# SIM_SCHE.net
KiCad netlist of a schematic drawn in Altium Designer
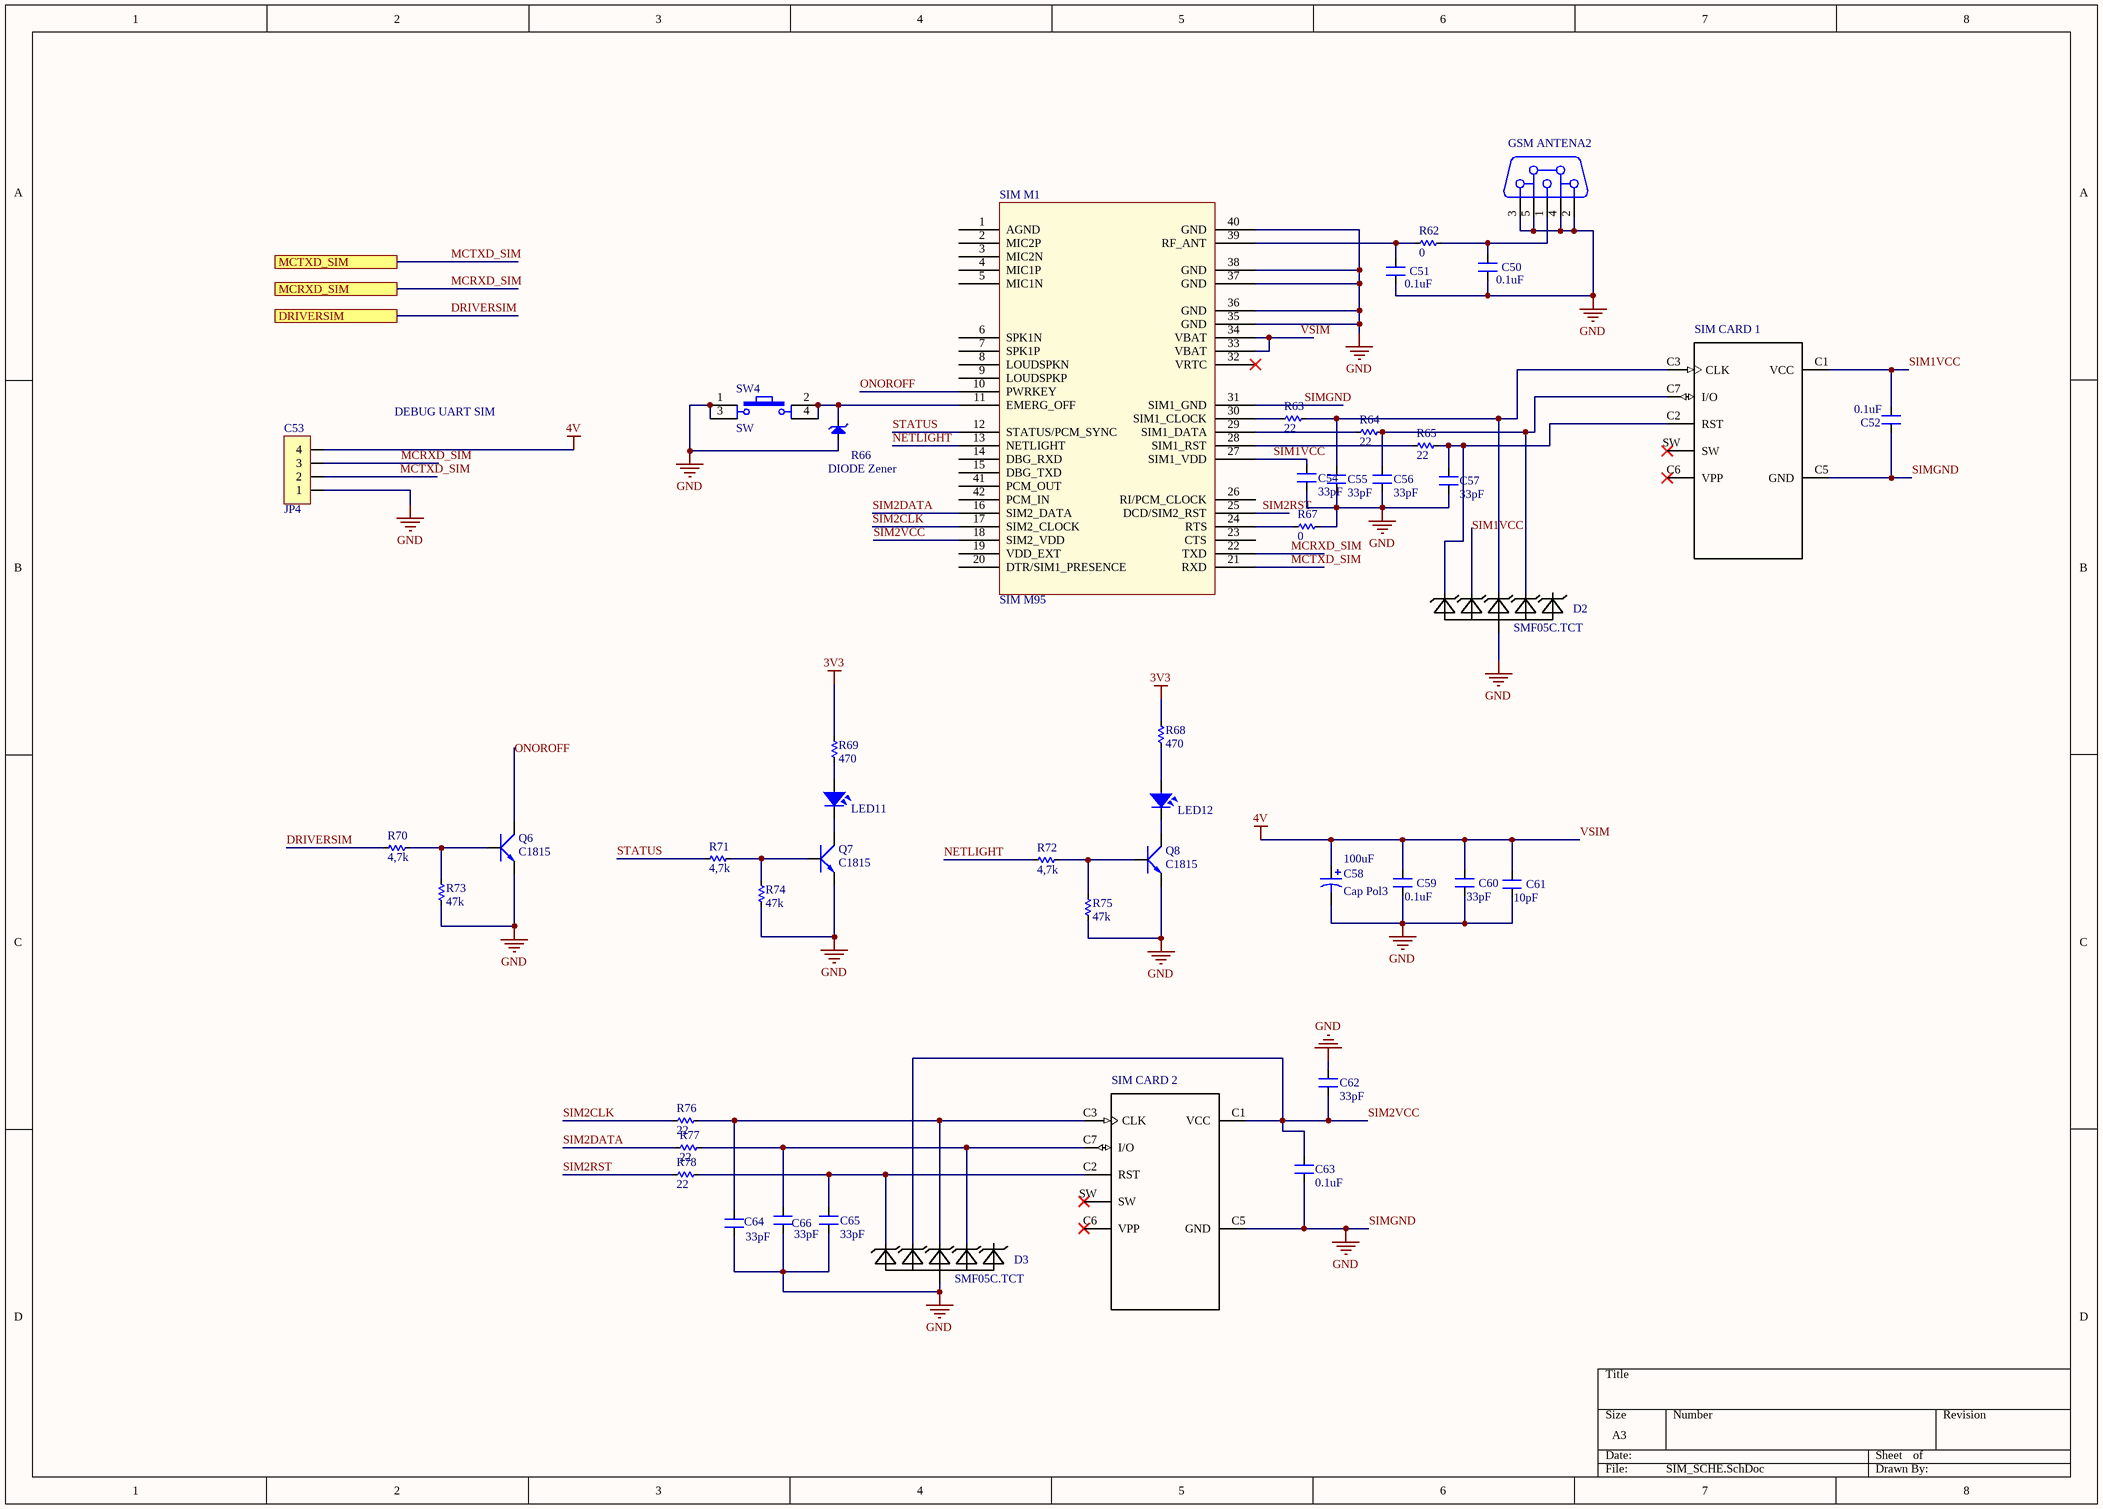
[diagram p0: SIM_SCHE.SchDoc]

(export (version "E")
  (design (tool "Eeschema 10.0.6"))
  (components
    (comp (ref "C50")
      (value "0.1uF")
      (footprint "res 0805 - duplicate")
      (description "Cap SMD")
      (libsource (lib "PART") (part "CM"))
    )
    (comp (ref "C51")
      (value "0.1uF")
      (footprint "res 0805 - duplicate")
      (description "Cap SMD")
      (libsource (lib "PART") (part "CM"))
    )
    (comp (ref "C52")
      (value "0.1uF")
      (footprint "res 0805 - duplicate")
      (description "Cap SMD")
      (libsource (lib "PART") (part "CM"))
    )
    (comp (ref "C53")
      (value "JP4")
      (footprint "JP4-C1T")
      (description "WR-PHD 2.54 mm Angled Socket Header")
      (fields
        (field (name "MANUFACTURER") "Würth Elektronik eiSos GmbH")
        (field (name "PARTNO") "613004143121")
        (field (name "CREATED BY") "Karrer Zheng")
      )
      (libsource (lib "LIBRARYabc") (part "JP4"))
    )
    (comp (ref "C54")
      (value "33pF")
      (footprint "res 0805 - duplicate")
      (fields (field (name "DESIGNED BY") "VanDungEvn"))
      (libsource (lib "syhaunguyen") (part "CN"))
    )
    (comp (ref "C55")
      (value "33pF")
      (footprint "res 0805 - duplicate")
      (fields (field (name "DESIGNED BY") "VanDungEvn"))
      (libsource (lib "syhaunguyen") (part "CN"))
    )
    (comp (ref "C56")
      (value "33pF")
      (footprint "res 0805 - duplicate")
      (fields (field (name "DESIGNED BY") "VanDungEvn"))
      (libsource (lib "syhaunguyen") (part "CN"))
    )
    (comp (ref "C57")
      (value "33pF")
      (footprint "res 0805 - duplicate")
      (fields (field (name "DESIGNED BY") "VanDungEvn"))
      (libsource (lib "syhaunguyen") (part "CN"))
    )
    (comp (ref "C58")
      (value "Cap Pol3")
      (footprint "cap_100uf")
      (description "Polarized Capacitor (Surface Mount)")
      (fields (field (name "ALTIUM_VALUE") "100uF") (field (name "PUBLISHER") "Altium Limited"))
      (libsource (lib "Miscellaneous Devices") (part "Cap Pol3"))
    )
    (comp (ref "C59")
      (value "0.1uF")
      (footprint "res 0805 - duplicate")
      (description "Cap SMD")
      (libsource (lib "PART") (part "CM"))
    )
    (comp (ref "C60")
      (value "33pF")
      (footprint "res 0805 - duplicate")
      (description "Cap SMD")
      (libsource (lib "PART") (part "CM"))
    )
    (comp (ref "C61")
      (value "10pF")
      (footprint "res 0805 - duplicate")
      (description "Cap SMD")
      (libsource (lib "PART") (part "CM"))
    )
    (comp (ref "C62")
      (value "33pF")
      (footprint "res 0805 - duplicate")
      (fields (field (name "DESIGNED BY") "VanDungEvn"))
      (libsource (lib "syhaunguyen") (part "CN"))
    )
    (comp (ref "C63")
      (value "0.1uF")
      (footprint "res 0805 - duplicate")
      (fields (field (name "DESIGNED BY") "VanDungEvn"))
      (libsource (lib "syhaunguyen") (part "CN"))
    )
    (comp (ref "C64")
      (value "33pF")
      (footprint "res 0805 - duplicate")
      (fields (field (name "DESIGNED BY") "VanDungEvn"))
      (libsource (lib "syhaunguyen") (part "CN"))
    )
    (comp (ref "C65")
      (value "33pF")
      (footprint "res 0805 - duplicate")
      (fields (field (name "DESIGNED BY") "VanDungEvn"))
      (libsource (lib "syhaunguyen") (part "CN"))
    )
    (comp (ref "C66")
      (value "33pF")
      (footprint "res 0805 - duplicate")
      (fields (field (name "DESIGNED BY") "VanDungEvn"))
      (libsource (lib "syhaunguyen") (part "CN"))
    )
    (comp (ref "D2")
      (value "SMF05C.TCT")
      (footprint "SC70-6")
      (fields (field (name "MF") "Semtech"))
      (libsource (lib "SMF05C.TCT") (part "SMF05C.TCT"))
    )
    (comp (ref "D3")
      (value "SMF05C.TCT")
      (footprint "SC70-6")
      (fields (field (name "MF") "Semtech"))
      (libsource (lib "SMF05C.TCT") (part "SMF05C.TCT"))
    )
    (comp (ref "GSM ANTENA2")
      (value "~")
      (footprint "anten")
      (description "CONNECTOR ANTEN")
      (fields
        (field (name "PARTNO") "210111003")
        (field (name "MANUFACTURER") "Würth Elektronik eiSos GmbH")
        (field (name "CREATED BY") "Christin Zierenner")
      )
      (libsource (lib "LIBRARYabc") (part "CON Ant"))
    )
    (comp (ref "LED11")
      (value "LED")
      (footprint "res 0805 - duplicate")
      (libsource (lib "LIBRARYabc") (part "LED SMD"))
    )
    (comp (ref "LED12")
      (value "LED")
      (footprint "res 0805 - duplicate")
      (libsource (lib "LIBRARYabc") (part "LED SMD"))
    )
    (comp (ref "Q6")
      (value "C1815")
      (footprint "SOT23B")
      (description "NPN 600mW, ECB")
      (libsource (lib "syhaunguyen") (part "C1815"))
    )
    (comp (ref "Q7")
      (value "C1815")
      (footprint "SOT23B")
      (description "NPN 600mW, ECB")
      (libsource (lib "syhaunguyen") (part "C1815"))
    )
    (comp (ref "Q8")
      (value "C1815")
      (footprint "SOT23B")
      (description "NPN 600mW, ECB")
      (libsource (lib "syhaunguyen") (part "C1815"))
    )
    (comp (ref "R62")
      (value "0")
      (footprint "res 0805 - duplicate")
      (description "Resistor")
      (fields
        (field (name "MANUFACTURER") "Generic Components")
        (field (name "PUBLISHER") "Altium Hobart Technology Centre")
      )
      (libsource (lib "LIBRARYabc") (part "Res-SMD"))
    )
    (comp (ref "R63")
      (value "22")
      (footprint "res 0805 - duplicate")
      (description "Resistor")
      (fields
        (field (name "MANUFACTURER") "Generic Components")
        (field (name "PUBLISHER") "Altium Hobart Technology Centre")
      )
      (libsource (lib "LIBRARYabc") (part "Res-SMD"))
    )
    (comp (ref "R64")
      (value "22")
      (footprint "res 0805 - duplicate")
      (description "Resistor")
      (fields
        (field (name "MANUFACTURER") "Generic Components")
        (field (name "PUBLISHER") "Altium Hobart Technology Centre")
      )
      (libsource (lib "LIBRARYabc") (part "Res-SMD"))
    )
    (comp (ref "R65")
      (value "22")
      (footprint "res 0805 - duplicate")
      (description "Resistor")
      (fields
        (field (name "MANUFACTURER") "Generic Components")
        (field (name "PUBLISHER") "Altium Hobart Technology Centre")
      )
      (libsource (lib "LIBRARYabc") (part "Res-SMD"))
    )
    (comp (ref "R66")
      (value "DIODE Zener")
      (footprint "diot zenner SOD123")
      (description "Zenner")
      (libsource (lib "LIBRARYabc") (part "DIODE Zener"))
    )
    (comp (ref "R67")
      (value "0")
      (footprint "res 0805 - duplicate")
      (description "Resistor")
      (fields
        (field (name "MANUFACTURER") "Generic Components")
        (field (name "PUBLISHER") "Altium Hobart Technology Centre")
      )
      (libsource (lib "LIBRARYabc") (part "Res-SMD"))
    )
    (comp (ref "R68")
      (value "470")
      (footprint "res 0805 - duplicate")
      (description "Resistor")
      (fields
        (field (name "MANUFACTURER") "Generic Components")
        (field (name "PUBLISHER") "Altium Hobart Technology Centre")
      )
      (libsource (lib "LIBRARYabc") (part "Res-SMD"))
    )
    (comp (ref "R69")
      (value "470")
      (footprint "res 0805 - duplicate")
      (description "Resistor")
      (fields
        (field (name "MANUFACTURER") "Generic Components")
        (field (name "PUBLISHER") "Altium Hobart Technology Centre")
      )
      (libsource (lib "LIBRARYabc") (part "Res-SMD"))
    )
    (comp (ref "R70")
      (value "4,7k")
      (footprint "res 0805 - duplicate")
      (description "Resistor")
      (fields
        (field (name "MANUFACTURER") "Generic Components")
        (field (name "PUBLISHER") "Altium Hobart Technology Centre")
      )
      (libsource (lib "LIBRARYabc") (part "Res-SMD"))
    )
    (comp (ref "R71")
      (value "4,7k")
      (footprint "res 0805 - duplicate")
      (description "Resistor")
      (fields
        (field (name "MANUFACTURER") "Generic Components")
        (field (name "PUBLISHER") "Altium Hobart Technology Centre")
      )
      (libsource (lib "LIBRARYabc") (part "Res-SMD"))
    )
    (comp (ref "R72")
      (value "4,7k")
      (footprint "res 0805 - duplicate")
      (description "Resistor")
      (fields
        (field (name "MANUFACTURER") "Generic Components")
        (field (name "PUBLISHER") "Altium Hobart Technology Centre")
      )
      (libsource (lib "LIBRARYabc") (part "Res-SMD"))
    )
    (comp (ref "R73")
      (value "47k")
      (footprint "res 0805 - duplicate")
      (description "Resistor")
      (fields
        (field (name "MANUFACTURER") "Generic Components")
        (field (name "PUBLISHER") "Altium Hobart Technology Centre")
      )
      (libsource (lib "LIBRARYabc") (part "Res-SMD"))
    )
    (comp (ref "R74")
      (value "47k")
      (footprint "res 0805 - duplicate")
      (description "Resistor")
      (fields
        (field (name "MANUFACTURER") "Generic Components")
        (field (name "PUBLISHER") "Altium Hobart Technology Centre")
      )
      (libsource (lib "LIBRARYabc") (part "Res-SMD"))
    )
    (comp (ref "R75")
      (value "47k")
      (footprint "res 0805 - duplicate")
      (description "Resistor")
      (fields
        (field (name "MANUFACTURER") "Generic Components")
        (field (name "PUBLISHER") "Altium Hobart Technology Centre")
      )
      (libsource (lib "LIBRARYabc") (part "Res-SMD"))
    )
    (comp (ref "R76")
      (value "22")
      (footprint "res 0805 - duplicate")
      (description "Resistor")
      (fields
        (field (name "MANUFACTURER") "Generic Components")
        (field (name "PUBLISHER") "Altium Hobart Technology Centre")
      )
      (libsource (lib "LIBRARYabc") (part "Res-SMD"))
    )
    (comp (ref "R77")
      (value "22")
      (footprint "res 0805 - duplicate")
      (description "Resistor")
      (fields
        (field (name "MANUFACTURER") "Generic Components")
        (field (name "PUBLISHER") "Altium Hobart Technology Centre")
      )
      (libsource (lib "LIBRARYabc") (part "Res-SMD"))
    )
    (comp (ref "R78")
      (value "22")
      (footprint "res 0805 - duplicate")
      (description "Resistor")
      (fields
        (field (name "MANUFACTURER") "Generic Components")
        (field (name "PUBLISHER") "Altium Hobart Technology Centre")
      )
      (libsource (lib "LIBRARYabc") (part "Res-SMD"))
    )
    (comp (ref "SIM CARD 1")
      (value "2199337-5")
      (footprint "SIMCARD")
      (description "ASS'Y FOR MICRO SIM H1.18 8POS _EMBOSS_")
      (fields (field (name "MF") "TE Connectivity"))
      (libsource (lib "2199337-5") (part "2199337-5"))
    )
    (comp (ref "SIM CARD 2")
      (value "2199337-5")
      (footprint "SIMCARD")
      (description "ASS'Y FOR MICRO SIM H1.18 8POS _EMBOSS_")
      (fields (field (name "MF") "TE Connectivity"))
      (libsource (lib "2199337-5") (part "2199337-5"))
    )
    (comp (ref "SIM M1") (value "SIM M95") (footprint "SIM M95") (libsource (lib "Sim M95") (part "SIM M95")))
    (comp (ref "SW4")
      (value "SW")
      (footprint "button")
      (description "Switch button 4 pin")
      (libsource (lib "syhaunguyen") (part "SW4"))
    )
  )
  (nets
    (net (code "1") (name "/DRIVERSIM") (class "Default")
      (node (ref "R70") (pin "2") (pinfunction "2_2") (pintype "passive"))
    )
    (net (code "2") (name "/MCRXD_SIM") (class "Default")
      (node (ref "C53") (pin "3") (pinfunction "3_3") (pintype "passive"))
      (node (ref "SIM M1") (pin "22") (pinfunction "TXD_22") (pintype "passive"))
    )
    (net (code "3") (name "/MCTXD_SIM") (class "Default")
      (node (ref "C53") (pin "2") (pinfunction "2_2") (pintype "passive"))
      (node (ref "SIM M1") (pin "21") (pinfunction "RXD_21") (pintype "passive"))
    )
    (net (code "4") (name "/NETLIGHT") (class "Default")
      (node (ref "R72") (pin "2") (pinfunction "2_2") (pintype "passive"))
      (node (ref "SIM M1") (pin "13") (pinfunction "NETLIGHT_13") (pintype "passive"))
    )
    (net (code "5") (name "/ONOROFF") (class "Default")
      (node (ref "Q6") (pin "2") (pinfunction "C_2") (pintype "passive"))
      (node (ref "SIM M1") (pin "10") (pinfunction "PWRKEY_10") (pintype "passive"))
    )
    (net (code "6") (name "/SIM1VCC") (class "Default")
      (node (ref "C52") (pin "2") (pinfunction "2_2") (pintype "passive"))
      (node (ref "C54") (pin "2") (pinfunction "2_2") (pintype "passive"))
      (node (ref "D2") (pin "3") (pinfunction "C2_3") (pintype "passive"))
      (node (ref "SIM CARD 1") (pin "C1") (pinfunction "VCC_C1") (pintype "power_in"))
      (node (ref "SIM M1") (pin "27") (pinfunction "SIM1_VDD_27") (pintype "passive"))
    )
    (net (code "7") (name "/SIM2CLK") (class "Default")
      (node (ref "R76") (pin "2") (pinfunction "2_2") (pintype "passive"))
      (node (ref "SIM M1") (pin "17") (pinfunction "SIM2_CLOCK_17") (pintype "passive"))
    )
    (net (code "8") (name "/SIM2DATA") (class "Default")
      (node (ref "R77") (pin "2") (pinfunction "2_2") (pintype "passive"))
      (node (ref "SIM M1") (pin "16") (pinfunction "SIM2_DATA_16") (pintype "passive"))
    )
    (net (code "9") (name "/SIM2RST") (class "Default")
      (node (ref "R78") (pin "2") (pinfunction "2_2") (pintype "passive"))
      (node (ref "SIM M1") (pin "25") (pinfunction "DCD/SIM2_RST_25") (pintype "passive"))
    )
    (net (code "10") (name "/SIM2VCC") (class "Default")
      (node (ref "C62") (pin "1") (pinfunction "1_1") (pintype "passive"))
      (node (ref "C63") (pin "2") (pinfunction "2_2") (pintype "passive"))
      (node (ref "D3") (pin "3") (pinfunction "C2_3") (pintype "passive"))
      (node (ref "SIM CARD 2") (pin "C1") (pinfunction "VCC_C1") (pintype "power_in"))
      (node (ref "SIM M1") (pin "18") (pinfunction "SIM2_VDD_18") (pintype "passive"))
    )
    (net (code "11") (name "/STATUS") (class "Default")
      (node (ref "R71") (pin "2") (pinfunction "2_2") (pintype "passive"))
      (node (ref "SIM M1") (pin "12") (pinfunction "STATUS/PCM_SYNC_12") (pintype "passive"))
    )
    (net (code "12") (name "3V3") (class "Default")
      (node (ref "R68") (pin "1") (pinfunction "1_1") (pintype "passive"))
      (node (ref "R69") (pin "1") (pinfunction "1_1") (pintype "passive"))
    )
    (net (code "13") (name "4V") (class "Default")
      (node (ref "C53") (pin "4") (pinfunction "4_4") (pintype "passive"))
      (node (ref "C58") (pin "1") (pinfunction "1_1") (pintype "passive"))
      (node (ref "C59") (pin "2") (pinfunction "2_2") (pintype "passive"))
      (node (ref "C60") (pin "2") (pinfunction "2_2") (pintype "passive"))
      (node (ref "C61") (pin "2") (pinfunction "2_2") (pintype "passive"))
      (node (ref "SIM M1") (pin "33") (pinfunction "VBAT_33") (pintype "passive"))
      (node (ref "SIM M1") (pin "34") (pinfunction "VBAT_34") (pintype "passive"))
    )
    (net (code "14") (name "GND") (class "Default")
      (node (ref "C50") (pin "1") (pinfunction "1_1") (pintype "passive"))
      (node (ref "C51") (pin "1") (pinfunction "1_1") (pintype "passive"))
      (node (ref "C52") (pin "1") (pinfunction "1_1") (pintype "passive"))
      (node (ref "C53") (pin "1") (pinfunction "1_1") (pintype "passive"))
      (node (ref "C54") (pin "1") (pinfunction "1_1") (pintype "passive"))
      (node (ref "C55") (pin "1") (pinfunction "1_1") (pintype "passive"))
      (node (ref "C56") (pin "1") (pinfunction "1_1") (pintype "passive"))
      (node (ref "C57") (pin "1") (pinfunction "1_1") (pintype "passive"))
      (node (ref "C58") (pin "2") (pinfunction "2_2") (pintype "passive"))
      (node (ref "C59") (pin "1") (pinfunction "1_1") (pintype "passive"))
      (node (ref "C60") (pin "1") (pinfunction "1_1") (pintype "passive"))
      (node (ref "C61") (pin "1") (pinfunction "1_1") (pintype "passive"))
      (node (ref "C62") (pin "2") (pinfunction "2_2") (pintype "passive"))
      (node (ref "C63") (pin "1") (pinfunction "1_1") (pintype "passive"))
      (node (ref "C64") (pin "1") (pinfunction "1_1") (pintype "passive"))
      (node (ref "C65") (pin "1") (pinfunction "1_1") (pintype "passive"))
      (node (ref "C66") (pin "1") (pinfunction "1_1") (pintype "passive"))
      (node (ref "D2") (pin "2") (pinfunction "A_2") (pintype "passive"))
      (node (ref "D3") (pin "2") (pinfunction "A_2") (pintype "passive"))
      (node (ref "GSM ANTENA2") (pin "2") (pinfunction "2_2") (pintype "passive"))
      (node (ref "GSM ANTENA2") (pin "3") (pinfunction "3_3") (pintype "passive"))
      (node (ref "GSM ANTENA2") (pin "4") (pinfunction "4_4") (pintype "passive"))
      (node (ref "GSM ANTENA2") (pin "5") (pinfunction "5_5") (pintype "passive"))
      (node (ref "Q6") (pin "1") (pinfunction "E_1") (pintype "passive"))
      (node (ref "Q7") (pin "1") (pinfunction "E_1") (pintype "passive"))
      (node (ref "Q8") (pin "1") (pinfunction "E_1") (pintype "passive"))
      (node (ref "R66") (pin "1") (pinfunction "A_1") (pintype "passive"))
      (node (ref "R67") (pin "2") (pinfunction "2_2") (pintype "passive"))
      (node (ref "R73") (pin "2") (pinfunction "2_2") (pintype "passive"))
      (node (ref "R74") (pin "2") (pinfunction "2_2") (pintype "passive"))
      (node (ref "R75") (pin "2") (pinfunction "2_2") (pintype "passive"))
      (node (ref "SIM CARD 1") (pin "C5") (pinfunction "GND_C5") (pintype "power_in"))
      (node (ref "SIM CARD 2") (pin "C5") (pinfunction "GND_C5") (pintype "power_in"))
      (node (ref "SIM M1") (pin "31") (pinfunction "SIM1_GND_31") (pintype "passive"))
      (node (ref "SIM M1") (pin "35") (pinfunction "GND_35") (pintype "passive"))
      (node (ref "SIM M1") (pin "36") (pinfunction "GND_36") (pintype "passive"))
      (node (ref "SIM M1") (pin "37") (pinfunction "GND_37") (pintype "passive"))
      (node (ref "SIM M1") (pin "38") (pinfunction "GND_38") (pintype "passive"))
      (node (ref "SIM M1") (pin "40") (pinfunction "GND_40") (pintype "passive"))
      (node (ref "SW4") (pin "1") (pintype "passive"))
      (node (ref "SW4") (pin "3") (pintype "passive"))
    )
    (net (code "15") (name "Net-(C50-Pad2)") (class "Default")
      (node (ref "C50") (pin "2") (pinfunction "2_2") (pintype "passive"))
      (node (ref "GSM ANTENA2") (pin "1") (pinfunction "1_1") (pintype "passive"))
      (node (ref "R62") (pin "2") (pinfunction "2_2") (pintype "passive"))
    )
    (net (code "16") (name "Net-(D2-C1)") (class "Default")
      (node (ref "C57") (pin "2") (pinfunction "2_2") (pintype "passive"))
      (node (ref "D2") (pin "1") (pinfunction "C1_1") (pintype "passive"))
      (node (ref "R65") (pin "2") (pinfunction "2_2") (pintype "passive"))
      (node (ref "SIM CARD 1") (pin "C2") (pinfunction "RST_C2") (pintype "passive"))
    )
    (net (code "17") (name "Net-(D2-C3)") (class "Default")
      (node (ref "C55") (pin "2") (pinfunction "2_2") (pintype "passive"))
      (node (ref "D2") (pin "4") (pinfunction "C3_4") (pintype "passive"))
      (node (ref "R63") (pin "2") (pinfunction "2_2") (pintype "passive"))
      (node (ref "SIM CARD 1") (pin "C3") (pinfunction "CLK_C3") (pintype "input"))
    )
    (net (code "18") (name "Net-(D2-C4)") (class "Default")
      (node (ref "C56") (pin "2") (pinfunction "2_2") (pintype "passive"))
      (node (ref "D2") (pin "5") (pinfunction "C4_5") (pintype "passive"))
      (node (ref "R64") (pin "2") (pinfunction "2_2") (pintype "passive"))
      (node (ref "SIM CARD 1") (pin "C7") (pinfunction "I/O_C7") (pintype "bidirectional"))
    )
    (net (code "19") (name "Net-(D3-C1)") (class "Default")
      (node (ref "C65") (pin "2") (pinfunction "2_2") (pintype "passive"))
      (node (ref "D3") (pin "1") (pinfunction "C1_1") (pintype "passive"))
      (node (ref "R78") (pin "1") (pinfunction "1_1") (pintype "passive"))
      (node (ref "SIM CARD 2") (pin "C2") (pinfunction "RST_C2") (pintype "passive"))
    )
    (net (code "20") (name "Net-(D3-C3)") (class "Default")
      (node (ref "C64") (pin "2") (pinfunction "2_2") (pintype "passive"))
      (node (ref "D3") (pin "4") (pinfunction "C3_4") (pintype "passive"))
      (node (ref "R76") (pin "1") (pinfunction "1_1") (pintype "passive"))
      (node (ref "SIM CARD 2") (pin "C3") (pinfunction "CLK_C3") (pintype "input"))
    )
    (net (code "21") (name "Net-(D3-C4)") (class "Default")
      (node (ref "C66") (pin "2") (pinfunction "2_2") (pintype "passive"))
      (node (ref "D3") (pin "5") (pinfunction "C4_5") (pintype "passive"))
      (node (ref "R77") (pin "1") (pinfunction "1_1") (pintype "passive"))
      (node (ref "SIM CARD 2") (pin "C7") (pinfunction "I/O_C7") (pintype "bidirectional"))
    )
    (net (code "22") (name "Net-(LED11-Pad1)") (class "Default")
      (node (ref "LED11") (pin "1") (pinfunction "1_1") (pintype "passive"))
      (node (ref "R69") (pin "2") (pinfunction "2_2") (pintype "passive"))
    )
    (net (code "23") (name "Net-(LED12-Pad1)") (class "Default")
      (node (ref "LED12") (pin "1") (pinfunction "1_1") (pintype "passive"))
      (node (ref "R68") (pin "2") (pinfunction "2_2") (pintype "passive"))
    )
    (net (code "24") (name "Net-(Q6-B)") (class "Default")
      (node (ref "Q6") (pin "3") (pinfunction "B_3") (pintype "passive"))
      (node (ref "R70") (pin "1") (pinfunction "1_1") (pintype "passive"))
      (node (ref "R73") (pin "1") (pinfunction "1_1") (pintype "passive"))
    )
    (net (code "25") (name "Net-(Q7-B)") (class "Default")
      (node (ref "Q7") (pin "3") (pinfunction "B_3") (pintype "passive"))
      (node (ref "R71") (pin "1") (pinfunction "1_1") (pintype "passive"))
      (node (ref "R74") (pin "1") (pinfunction "1_1") (pintype "passive"))
    )
    (net (code "26") (name "Net-(Q7-C)") (class "Default")
      (node (ref "LED11") (pin "2") (pinfunction "2_2") (pintype "passive"))
      (node (ref "Q7") (pin "2") (pinfunction "C_2") (pintype "passive"))
    )
    (net (code "27") (name "Net-(Q8-B)") (class "Default")
      (node (ref "Q8") (pin "3") (pinfunction "B_3") (pintype "passive"))
      (node (ref "R72") (pin "1") (pinfunction "1_1") (pintype "passive"))
      (node (ref "R75") (pin "1") (pinfunction "1_1") (pintype "passive"))
    )
    (net (code "28") (name "Net-(Q8-C)") (class "Default")
      (node (ref "LED12") (pin "2") (pinfunction "2_2") (pintype "passive"))
      (node (ref "Q8") (pin "2") (pinfunction "C_2") (pintype "passive"))
    )
    (net (code "29") (name "Net-(R66-K)") (class "Default")
      (node (ref "R66") (pin "2") (pinfunction "K_2") (pintype "passive"))
      (node (ref "SIM M1") (pin "11") (pinfunction "EMERG_OFF_11") (pintype "passive"))
      (node (ref "SW4") (pin "2") (pintype "passive"))
      (node (ref "SW4") (pin "4") (pintype "passive"))
    )
    (net (code "30") (name "Net-(SIM M1-RF_ANT)") (class "Default")
      (node (ref "C51") (pin "2") (pinfunction "2_2") (pintype "passive"))
      (node (ref "R62") (pin "1") (pinfunction "1_1") (pintype "passive"))
      (node (ref "SIM M1") (pin "39") (pinfunction "RF_ANT_39") (pintype "passive"))
    )
    (net (code "31") (name "Net-(SIM M1-RTS)") (class "Default")
      (node (ref "R67") (pin "1") (pinfunction "1_1") (pintype "passive"))
      (node (ref "SIM M1") (pin "24") (pinfunction "RTS_24") (pintype "passive"))
    )
    (net (code "32") (name "Net-(SIM M1-SIM1_CLOCK)") (class "Default")
      (node (ref "R63") (pin "1") (pinfunction "1_1") (pintype "passive"))
      (node (ref "SIM M1") (pin "30") (pinfunction "SIM1_CLOCK_30") (pintype "passive"))
    )
    (net (code "33") (name "Net-(SIM M1-SIM1_DATA)") (class "Default")
      (node (ref "R64") (pin "1") (pinfunction "1_1") (pintype "passive"))
      (node (ref "SIM M1") (pin "29") (pinfunction "SIM1_DATA_29") (pintype "passive"))
    )
    (net (code "34") (name "Net-(SIM M1-SIM1_RST)") (class "Default")
      (node (ref "R65") (pin "1") (pinfunction "1_1") (pintype "passive"))
      (node (ref "SIM M1") (pin "28") (pinfunction "SIM1_RST_28") (pintype "passive"))
    )
    (net (code "35") (name "unconnected-(D2-C5-Pad6)") (class "Default")
      (node (ref "D2") (pin "6") (pinfunction "C5_6") (pintype "passive"))
    )
    (net (code "36") (name "unconnected-(D3-C5-Pad6)") (class "Default")
      (node (ref "D3") (pin "6") (pinfunction "C5_6") (pintype "passive"))
    )
    (net (code "37") (name "unconnected-(SIM CARD 1-PadSW)") (class "Default")
      (node (ref "SIM CARD 1") (pin "SW") (pinfunction "SW_SW") (pintype "passive+no_connect"))
    )
    (net (code "38") (name "unconnected-(SIM CARD 1-VPP-PadC6)") (class "Default")
      (node (ref "SIM CARD 1") (pin "C6") (pinfunction "VPP_C6") (pintype "passive+no_connect"))
    )
    (net (code "39") (name "unconnected-(SIM CARD 2-PadSW)") (class "Default")
      (node (ref "SIM CARD 2") (pin "SW") (pinfunction "SW_SW") (pintype "passive+no_connect"))
    )
    (net (code "40") (name "unconnected-(SIM CARD 2-VPP-PadC6)") (class "Default")
      (node (ref "SIM CARD 2") (pin "C6") (pinfunction "VPP_C6") (pintype "passive+no_connect"))
    )
    (net (code "41") (name "unconnected-(SIM M1-AGND-Pad1)") (class "Default")
      (node (ref "SIM M1") (pin "1") (pinfunction "AGND_1") (pintype "passive"))
    )
    (net (code "42") (name "unconnected-(SIM M1-CTS-Pad23)") (class "Default")
      (node (ref "SIM M1") (pin "23") (pinfunction "CTS_23") (pintype "passive"))
    )
    (net (code "43") (name "unconnected-(SIM M1-DBG_RXD-Pad14)") (class "Default")
      (node (ref "SIM M1") (pin "14") (pinfunction "DBG_RXD_14") (pintype "passive"))
    )
    (net (code "44") (name "unconnected-(SIM M1-DBG_TXD-Pad15)") (class "Default")
      (node (ref "SIM M1") (pin "15") (pinfunction "DBG_TXD_15") (pintype "passive"))
    )
    (net (code "45") (name "unconnected-(SIM M1-DTR{slash}SIM1_PRESENCE-Pad20)") (class "Default")
      (node (ref "SIM M1") (pin "20") (pinfunction "DTR/SIM1_PRESENCE_20") (pintype "passive"))
    )
    (net (code "46") (name "unconnected-(SIM M1-LOUDSPKN-Pad8)") (class "Default")
      (node (ref "SIM M1") (pin "8") (pinfunction "LOUDSPKN_8") (pintype "passive"))
    )
    (net (code "47") (name "unconnected-(SIM M1-LOUDSPKP-Pad9)") (class "Default")
      (node (ref "SIM M1") (pin "9") (pinfunction "LOUDSPKP_9") (pintype "passive"))
    )
    (net (code "48") (name "unconnected-(SIM M1-MIC1N-Pad5)") (class "Default")
      (node (ref "SIM M1") (pin "5") (pinfunction "MIC1N_5") (pintype "passive"))
    )
    (net (code "49") (name "unconnected-(SIM M1-MIC1P-Pad4)") (class "Default")
      (node (ref "SIM M1") (pin "4") (pinfunction "MIC1P_4") (pintype "passive"))
    )
    (net (code "50") (name "unconnected-(SIM M1-MIC2N-Pad3)") (class "Default")
      (node (ref "SIM M1") (pin "3") (pinfunction "MIC2N_3") (pintype "passive"))
    )
    (net (code "51") (name "unconnected-(SIM M1-MIC2P-Pad2)") (class "Default")
      (node (ref "SIM M1") (pin "2") (pinfunction "MIC2P_2") (pintype "passive"))
    )
    (net (code "52") (name "unconnected-(SIM M1-PCM_IN-Pad42)") (class "Default")
      (node (ref "SIM M1") (pin "42") (pinfunction "PCM_IN_42") (pintype "passive"))
    )
    (net (code "53") (name "unconnected-(SIM M1-PCM_OUT-Pad41)") (class "Default")
      (node (ref "SIM M1") (pin "41") (pinfunction "PCM_OUT_41") (pintype "passive"))
    )
    (net (code "54") (name "unconnected-(SIM M1-RI{slash}PCM_CLOCK-Pad26)") (class "Default")
      (node (ref "SIM M1") (pin "26") (pinfunction "RI/PCM_CLOCK_26") (pintype "passive"))
    )
    (net (code "55") (name "unconnected-(SIM M1-SPK1N-Pad6)") (class "Default")
      (node (ref "SIM M1") (pin "6") (pinfunction "SPK1N_6") (pintype "passive"))
    )
    (net (code "56") (name "unconnected-(SIM M1-SPK1P-Pad7)") (class "Default")
      (node (ref "SIM M1") (pin "7") (pinfunction "SPK1P_7") (pintype "passive"))
    )
    (net (code "57") (name "unconnected-(SIM M1-VDD_EXT-Pad19)") (class "Default")
      (node (ref "SIM M1") (pin "19") (pinfunction "VDD_EXT_19") (pintype "passive"))
    )
    (net (code "58") (name "unconnected-(SIM M1-VRTC-Pad32)") (class "Default")
      (node (ref "SIM M1") (pin "32") (pinfunction "VRTC_32") (pintype "passive+no_connect"))
    )
  )
)
